# FPGA_CONFIG.net
KiCad netlist of a schematic drawn in Altium Designer
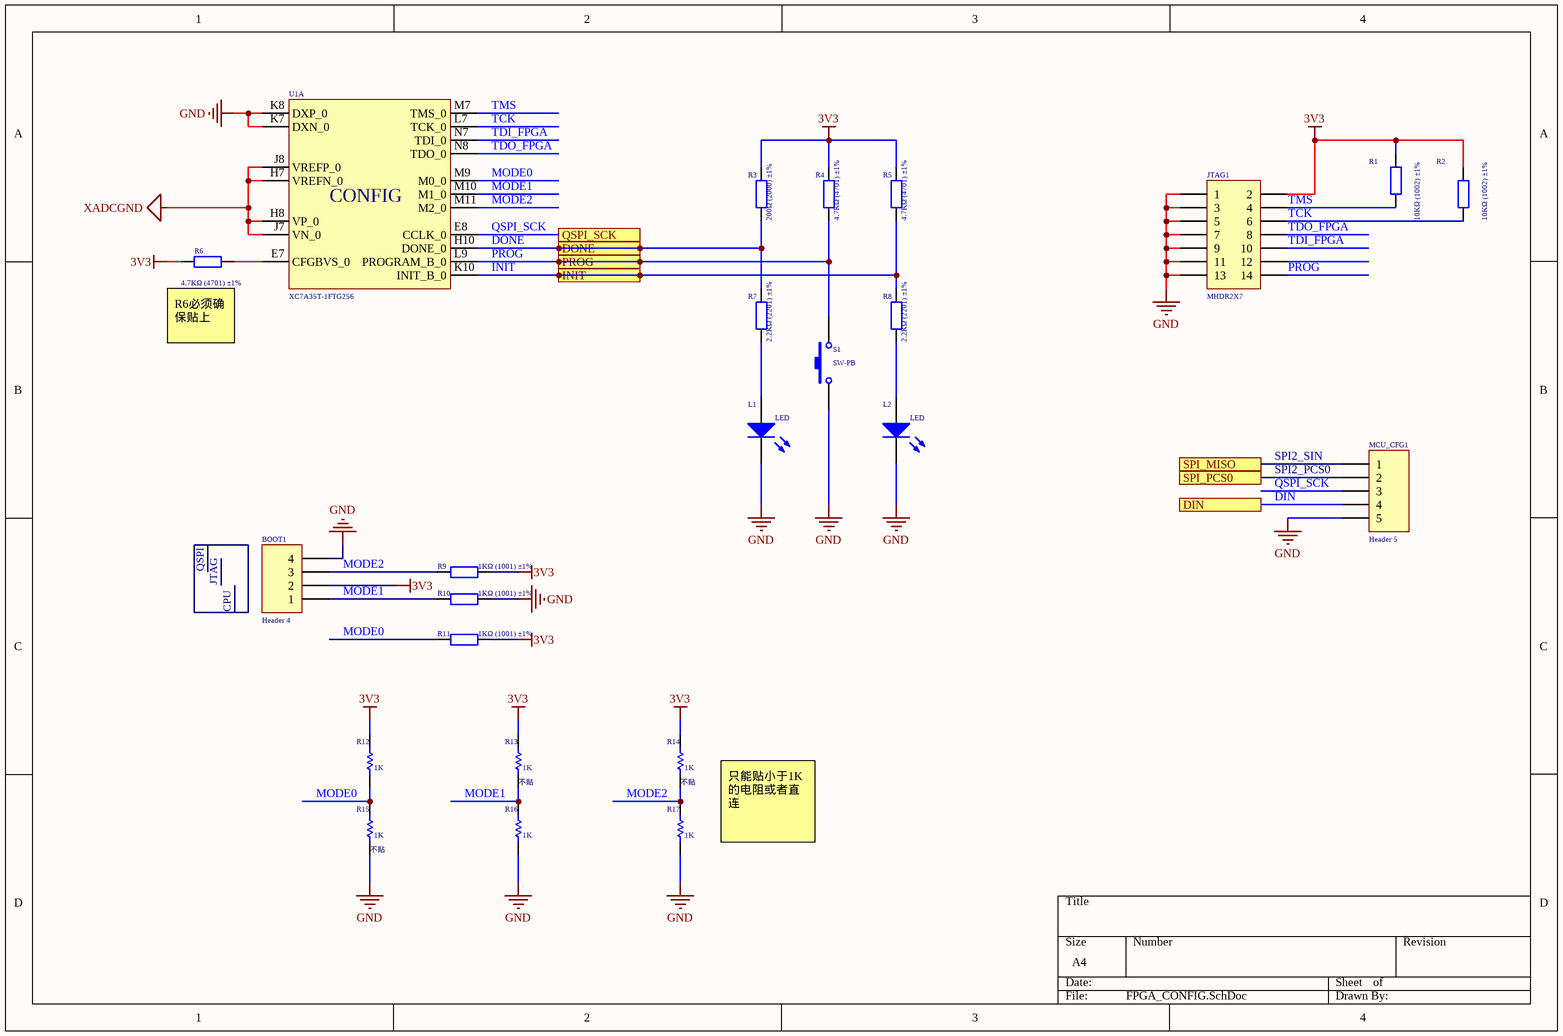
[diagram p0: FPGA_CONFIG.SchDoc]

(export (version "E")
  (design (tool "Eeschema 10.0.6"))
  (components
    (comp (ref "BOOT1")
      (value "Header 4")
      (footprint "HDR1X4")
      (description "Header, 4-Pin")
      (fields (field (name "PUBLISHER") "Altium Limited"))
      (libsource (lib "Sparks") (part "Header 4"))
    )
    (comp (ref "JTAG1")
      (value "MHDR2X7")
      (footprint "SMT7*2-2MM")
      (description "Header, 7-Pin, Dual row")
      (fields (field (name "PUBLISHER") "Altium Limited"))
      (libsource (lib "Miscellaneous Connectors") (part "MHDR2X7"))
    )
    (comp (ref "L1") (value "LED") (footprint "1608[0603]") (libsource (lib "Sparks") (part "LED")))
    (comp (ref "L2") (value "LED") (footprint "1608[0603]") (libsource (lib "Sparks") (part "LED")))
    (comp (ref "MCU_CFG1")
      (value "Header 5")
      (footprint "MHDR1X5")
      (description "Header, 5-Pin")
      (fields (field (name "PUBLISHER") "Altium Limited"))
      (libsource (lib "Sparks") (part "Header 5"))
    )
    (comp (ref "R1")
      (value "10KΩ (1002) ±1%")
      (footprint "0402_R")
      (description "贴片电阻")
      (libsource (lib "RES") (part "0402 10KΩ (1002) 1%"))
    )
    (comp (ref "R2")
      (value "10KΩ (1002) ±1%")
      (footprint "0402_R")
      (description "贴片电阻")
      (libsource (lib "RES") (part "0402 10KΩ (1002) 1%"))
    )
    (comp (ref "R3")
      (value "200Ω (2000) ±1%")
      (footprint "0402_R")
      (description "贴片电阻")
      (libsource (lib "RES") (part "0402 200Ω (2000) 1%"))
    )
    (comp (ref "R4")
      (value "4.7KΩ (4701) ±1%")
      (footprint "0402_R")
      (description "贴片电阻")
      (libsource (lib "RES") (part "0402 4.7KΩ (4701) 1%"))
    )
    (comp (ref "R5")
      (value "4.7KΩ (4701) ±1%")
      (footprint "0402_R")
      (description "贴片电阻")
      (libsource (lib "RES") (part "0402 4.7KΩ (4701) 1%"))
    )
    (comp (ref "R6")
      (value "4.7KΩ (4701) ±1%")
      (footprint "0402_R")
      (description "贴片电阻")
      (libsource (lib "") (part "0402 4.7KΩ (4701) 1%_1"))
    )
    (comp (ref "R7")
      (value "2.2KΩ (2201) ±1%")
      (footprint "0402_R")
      (description "贴片电阻")
      (libsource (lib "Miscellaneous Devices LC") (part "0402 2.2KΩ (2201) 1%"))
    )
    (comp (ref "R8")
      (value "2.2KΩ (2201) ±1%")
      (footprint "0402_R")
      (description "贴片电阻")
      (libsource (lib "Miscellaneous Devices LC") (part "0402 2.2KΩ (2201) 1%"))
    )
    (comp (ref "R9")
      (value "1KΩ (1001) ±1%")
      (footprint "0402_R")
      (description "贴片电阻")
      (libsource (lib "Miscellaneous Devices LC") (part "0402 1KΩ (1001) 1%"))
    )
    (comp (ref "R10")
      (value "1KΩ (1001) ±1%")
      (footprint "0402_R")
      (description "贴片电阻")
      (libsource (lib "Miscellaneous Devices LC") (part "0402 1KΩ (1001) 1%"))
    )
    (comp (ref "R11")
      (value "1KΩ (1001) ±1%")
      (footprint "0402_R")
      (description "贴片电阻")
      (libsource (lib "Miscellaneous Devices LC") (part "0402 1KΩ (1001) 1%"))
    )
    (comp (ref "R12")
      (value "1K")
      (footprint "1608[0603]")
      (description "贴片电阻")
      (fields (field (name "Comment") "Res") (field (name "PUBLISHER") "Altium Limited"))
      (libsource (lib "Sparks") (part "Res"))
    )
    (comp (ref "R13")
      (value "不贴")
      (footprint "1608[0603]")
      (description "贴片电阻")
      (fields (field (name "ALTIUM_VALUE") "1K") (field (name "PUBLISHER") "Altium Limited"))
      (libsource (lib "Sparks") (part "Res"))
    )
    (comp (ref "R14")
      (value "不贴")
      (footprint "1608[0603]")
      (description "贴片电阻")
      (fields (field (name "ALTIUM_VALUE") "1K") (field (name "PUBLISHER") "Altium Limited"))
      (libsource (lib "Sparks") (part "Res"))
    )
    (comp (ref "R15")
      (value "不贴")
      (footprint "1608[0603]")
      (description "贴片电阻")
      (fields (field (name "ALTIUM_VALUE") "1K") (field (name "PUBLISHER") "Altium Limited"))
      (libsource (lib "Sparks") (part "Res"))
    )
    (comp (ref "R16")
      (value "1K")
      (footprint "1608[0603]")
      (description "贴片电阻")
      (fields (field (name "Comment") "Res") (field (name "PUBLISHER") "Altium Limited"))
      (libsource (lib "Sparks") (part "Res"))
    )
    (comp (ref "R17")
      (value "1K")
      (footprint "1608[0603]")
      (description "贴片电阻")
      (fields (field (name "Comment") "Res") (field (name "PUBLISHER") "Altium Limited"))
      (libsource (lib "Sparks") (part "Res"))
    )
    (comp (ref "S1")
      (value "SW-PB")
      (footprint "key 3*4*2")
      (description "Switch")
      (fields (field (name "PUBLISHER") "Altium Limited"))
      (libsource (lib "Miscellaneous Devices") (part "SW-PB"))
    )
    (comp (ref "U1")
      (value "XC7A35T-1FTG256")
      (footprint "BGA100P9X9-81A")
      (libsource (lib "Schlib") (part "XC7A35T-1FTG256"))
    )
  )
  (nets
    (net (code "1") (name "/DIN") (class "Default")
      (node (ref "MCU_CFG1") (pin "4") (pinfunction "4_4") (pintype "passive"))
    )
    (net (code "2") (name "/DONE") (class "Default")
      (node (ref "R3") (pin "1") (pinfunction "1_1") (pintype "passive"))
      (node (ref "R7") (pin "2") (pinfunction "2_2") (pintype "passive"))
      (node (ref "U1") (pin "H10") (pinfunction "DONE_0_H10") (pintype "passive"))
    )
    (net (code "3") (name "/INIT") (class "Default")
      (node (ref "R5") (pin "1") (pinfunction "1_1") (pintype "passive"))
      (node (ref "R8") (pin "2") (pinfunction "2_2") (pintype "passive"))
      (node (ref "U1") (pin "K10") (pinfunction "INIT_B_0_K10") (pintype "passive"))
    )
    (net (code "4") (name "/MODE0") (class "Default")
      (node (ref "R11") (pin "1") (pinfunction "1_1") (pintype "passive"))
      (node (ref "R12") (pin "1") (pinfunction "1_1") (pintype "passive"))
      (node (ref "R15") (pin "2") (pinfunction "2_2") (pintype "passive"))
      (node (ref "U1") (pin "M9") (pinfunction "M0_0_M9") (pintype "passive"))
    )
    (net (code "5") (name "/MODE1") (class "Default")
      (node (ref "BOOT1") (pin "1") (pinfunction "1_1") (pintype "passive"))
      (node (ref "R10") (pin "1") (pinfunction "1_1") (pintype "passive"))
      (node (ref "R13") (pin "1") (pinfunction "1_1") (pintype "passive"))
      (node (ref "R16") (pin "2") (pinfunction "2_2") (pintype "passive"))
      (node (ref "U1") (pin "M10") (pinfunction "M1_0_M10") (pintype "passive"))
    )
    (net (code "6") (name "/MODE2") (class "Default")
      (node (ref "BOOT1") (pin "3") (pinfunction "3_3") (pintype "passive"))
      (node (ref "R14") (pin "1") (pinfunction "1_1") (pintype "passive"))
      (node (ref "R17") (pin "2") (pinfunction "2_2") (pintype "passive"))
      (node (ref "R9") (pin "1") (pinfunction "1_1") (pintype "passive"))
      (node (ref "U1") (pin "M11") (pinfunction "M2_0_M11") (pintype "passive"))
    )
    (net (code "7") (name "/PROG") (class "Default")
      (node (ref "JTAG1") (pin "14") (pinfunction "14_14") (pintype "passive"))
      (node (ref "R4") (pin "1") (pinfunction "1_1") (pintype "passive"))
      (node (ref "S1") (pin "2") (pinfunction "2_2") (pintype "passive"))
      (node (ref "U1") (pin "L9") (pinfunction "PROGRAM_B_0_L9") (pintype "passive"))
    )
    (net (code "8") (name "/QSPI_SCK") (class "Default")
      (node (ref "MCU_CFG1") (pin "3") (pinfunction "3_3") (pintype "passive"))
      (node (ref "U1") (pin "E8") (pinfunction "CCLK_0_E8") (pintype "passive"))
    )
    (net (code "9") (name "/SPI2_PCS0") (class "Default")
      (node (ref "MCU_CFG1") (pin "2") (pinfunction "2_2") (pintype "passive"))
    )
    (net (code "10") (name "/SPI2_SIN") (class "Default")
      (node (ref "MCU_CFG1") (pin "1") (pinfunction "1_1") (pintype "passive"))
    )
    (net (code "11") (name "/TCK") (class "Default")
      (node (ref "JTAG1") (pin "6") (pinfunction "6_6") (pintype "passive"))
      (node (ref "R2") (pin "1") (pinfunction "1_1") (pintype "passive"))
      (node (ref "U1") (pin "L7") (pinfunction "TCK_0_L7") (pintype "passive"))
    )
    (net (code "12") (name "/TDI_FPGA") (class "Default")
      (node (ref "JTAG1") (pin "10") (pinfunction "10_10") (pintype "passive"))
      (node (ref "U1") (pin "N7") (pinfunction "TDI_0_N7") (pintype "passive"))
    )
    (net (code "13") (name "/TDO_FPGA") (class "Default")
      (node (ref "JTAG1") (pin "8") (pinfunction "8_8") (pintype "passive"))
      (node (ref "U1") (pin "N8") (pinfunction "TDO_0_N8") (pintype "passive"))
    )
    (net (code "14") (name "/TMS") (class "Default")
      (node (ref "JTAG1") (pin "4") (pinfunction "4_4") (pintype "passive"))
      (node (ref "R1") (pin "1") (pinfunction "1_1") (pintype "passive"))
      (node (ref "U1") (pin "M7") (pinfunction "TMS_0_M7") (pintype "passive"))
    )
    (net (code "15") (name "3V3") (class "Default")
      (node (ref "BOOT1") (pin "2") (pinfunction "2_2") (pintype "passive"))
      (node (ref "JTAG1") (pin "2") (pinfunction "2_2") (pintype "passive"))
      (node (ref "R1") (pin "2") (pinfunction "2_2") (pintype "passive"))
      (node (ref "R11") (pin "2") (pinfunction "2_2") (pintype "passive"))
      (node (ref "R12") (pin "2") (pinfunction "2_2") (pintype "passive"))
      (node (ref "R13") (pin "2") (pinfunction "2_2") (pintype "passive"))
      (node (ref "R14") (pin "2") (pinfunction "2_2") (pintype "passive"))
      (node (ref "R2") (pin "2") (pinfunction "2_2") (pintype "passive"))
      (node (ref "R3") (pin "2") (pinfunction "2_2") (pintype "passive"))
      (node (ref "R4") (pin "2") (pinfunction "2_2") (pintype "passive"))
      (node (ref "R5") (pin "2") (pinfunction "2_2") (pintype "passive"))
      (node (ref "R6") (pin "1") (pinfunction "1_1") (pintype "passive"))
      (node (ref "R9") (pin "2") (pinfunction "2_2") (pintype "passive"))
    )
    (net (code "16") (name "GND") (class "Default")
      (node (ref "BOOT1") (pin "4") (pinfunction "4_4") (pintype "passive"))
      (node (ref "JTAG1") (pin "1") (pinfunction "1_1") (pintype "passive"))
      (node (ref "JTAG1") (pin "11") (pinfunction "11_11") (pintype "passive"))
      (node (ref "JTAG1") (pin "13") (pinfunction "13_13") (pintype "passive"))
      (node (ref "JTAG1") (pin "3") (pinfunction "3_3") (pintype "passive"))
      (node (ref "JTAG1") (pin "5") (pinfunction "5_5") (pintype "passive"))
      (node (ref "JTAG1") (pin "7") (pinfunction "7_7") (pintype "passive"))
      (node (ref "JTAG1") (pin "9") (pinfunction "9_9") (pintype "passive"))
      (node (ref "L1") (pin "2") (pinfunction "K_2") (pintype "passive"))
      (node (ref "L2") (pin "2") (pinfunction "K_2") (pintype "passive"))
      (node (ref "MCU_CFG1") (pin "5") (pinfunction "5_5") (pintype "passive"))
      (node (ref "R10") (pin "2") (pinfunction "2_2") (pintype "passive"))
      (node (ref "R15") (pin "1") (pinfunction "1_1") (pintype "passive"))
      (node (ref "R16") (pin "1") (pinfunction "1_1") (pintype "passive"))
      (node (ref "R17") (pin "1") (pinfunction "1_1") (pintype "passive"))
      (node (ref "S1") (pin "1") (pinfunction "1_1") (pintype "passive"))
      (node (ref "U1") (pin "K7") (pinfunction "DXN_0_K7") (pintype "passive"))
      (node (ref "U1") (pin "K8") (pinfunction "DXP_0_K8") (pintype "passive"))
    )
    (net (code "17") (name "Net-(L1-A)") (class "Default")
      (node (ref "L1") (pin "1") (pinfunction "A_1") (pintype "passive"))
      (node (ref "R7") (pin "1") (pinfunction "1_1") (pintype "passive"))
    )
    (net (code "18") (name "Net-(L2-A)") (class "Default")
      (node (ref "L2") (pin "1") (pinfunction "A_1") (pintype "passive"))
      (node (ref "R8") (pin "1") (pinfunction "1_1") (pintype "passive"))
    )
    (net (code "19") (name "Net-(U1A-CFGBVS_0)") (class "Default")
      (node (ref "R6") (pin "2") (pinfunction "2_2") (pintype "passive"))
      (node (ref "U1") (pin "E7") (pinfunction "CFGBVS_0_E7") (pintype "passive"))
    )
    (net (code "20") (name "XADCGND") (class "Default")
      (node (ref "U1") (pin "H7") (pinfunction "VREFN_0_H7") (pintype "passive"))
      (node (ref "U1") (pin "H8") (pinfunction "VP_0_H8") (pintype "passive"))
      (node (ref "U1") (pin "J7") (pinfunction "VN_0_J7") (pintype "passive"))
      (node (ref "U1") (pin "J8") (pinfunction "VREFP_0_J8") (pintype "passive"))
    )
    (net (code "21") (name "unconnected-(JTAG1-Pad12)") (class "Default")
      (node (ref "JTAG1") (pin "12") (pinfunction "12_12") (pintype "passive"))
    )
  )
)
